# Sequencer2.net
KiCad netlist of a schematic drawn in EAGLE
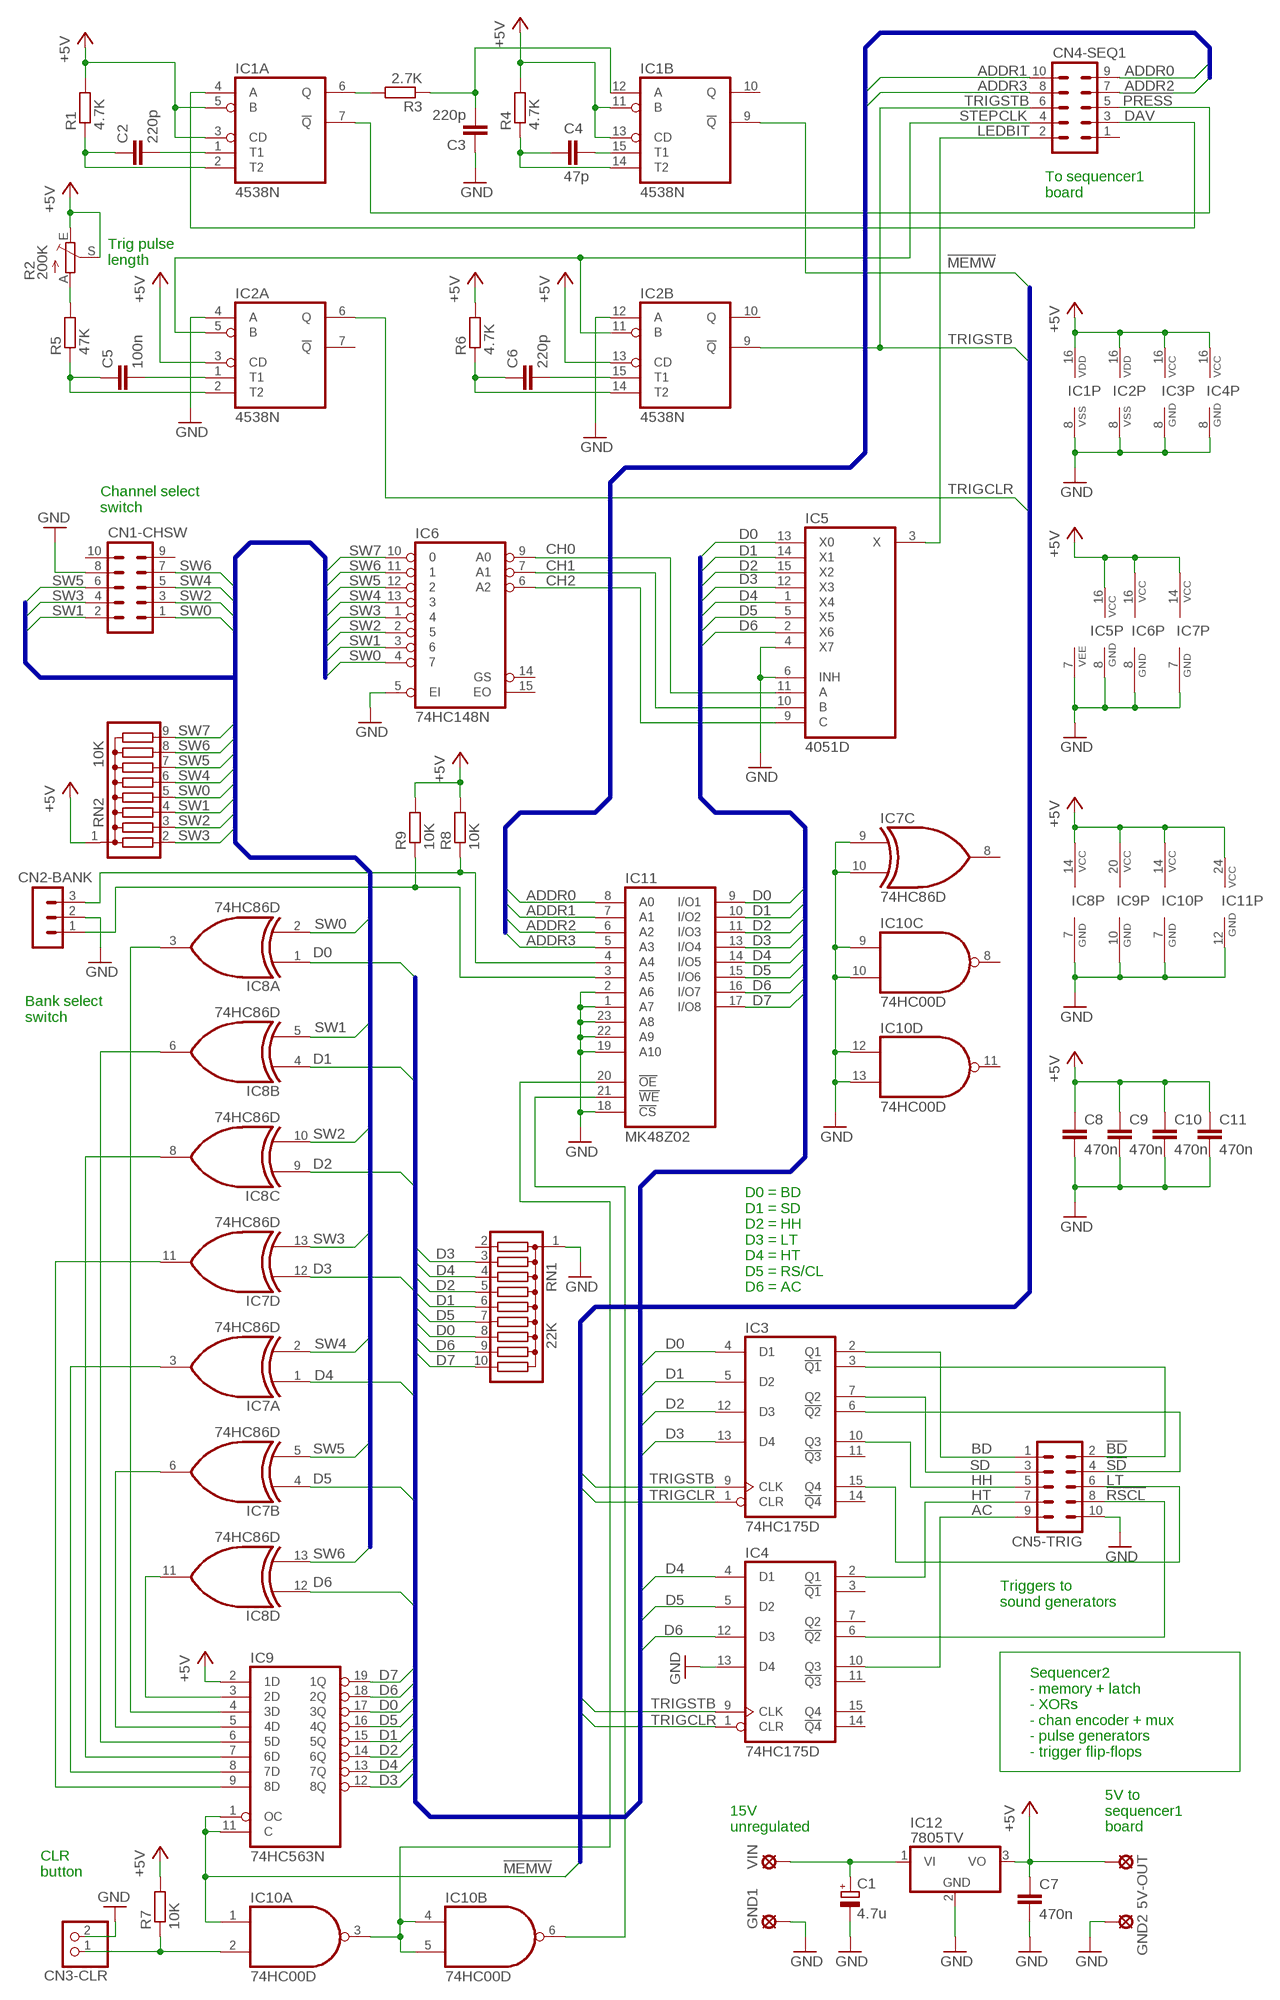
[diagram p0: schematic, sheet 1]

(export (version "E")
  (design (tool "Eeschema 10.0.6"))
  (components
    (comp (ref "5V-OUT")
      (value "LSP10")
      (footprint "eagle-import:LSP10")
      (libsource (lib "eagle-import") (part "LSP10"))
    )
    (comp (ref "C1")
      (value "4.7u")
      (footprint "eagle-import:SMC_A")
      (libsource (lib "eagle-import") (part "CPOL-EUSMCA"))
    )
    (comp (ref "C2")
      (value "220p")
      (footprint "eagle-import:C0805")
      (libsource (lib "eagle-import") (part "C-EUC0805"))
    )
    (comp (ref "C3")
      (value "220p")
      (footprint "eagle-import:C0805")
      (libsource (lib "eagle-import") (part "C-EUC0805"))
    )
    (comp (ref "C4")
      (value "47p")
      (footprint "eagle-import:C0805")
      (libsource (lib "eagle-import") (part "C-EUC0805"))
    )
    (comp (ref "C5")
      (value "100n")
      (footprint "eagle-import:C0805")
      (libsource (lib "eagle-import") (part "C-EUC0805"))
    )
    (comp (ref "C6")
      (value "220p")
      (footprint "eagle-import:C0805")
      (libsource (lib "eagle-import") (part "C-EUC0805"))
    )
    (comp (ref "C7")
      (value "470n")
      (footprint "eagle-import:C0603")
      (libsource (lib "eagle-import") (part "C-EUC0603"))
    )
    (comp (ref "C8")
      (value "470n")
      (footprint "eagle-import:C0603")
      (libsource (lib "eagle-import") (part "C-EUC0603"))
    )
    (comp (ref "C9")
      (value "470n")
      (footprint "eagle-import:C0603")
      (libsource (lib "eagle-import") (part "C-EUC0603"))
    )
    (comp (ref "C10")
      (value "470n")
      (footprint "eagle-import:C0603")
      (libsource (lib "eagle-import") (part "C-EUC0603"))
    )
    (comp (ref "C11")
      (value "470n")
      (footprint "eagle-import:C0603")
      (libsource (lib "eagle-import") (part "C-EUC0603"))
    )
    (comp (ref "CN1-CHSW")
      (value "MA05-2")
      (footprint "eagle-import:MA05-2")
      (libsource (lib "eagle-import") (part "MA05-2"))
    )
    (comp (ref "CN2-BANK")
      (value "MA03-1")
      (footprint "eagle-import:MA03-1")
      (libsource (lib "eagle-import") (part "MA03-1"))
    )
    (comp (ref "CN3-CLR")
      (value "PINHD-1X2")
      (footprint "eagle-import:1X02")
      (libsource (lib "eagle-import") (part "PINHD-1X2"))
    )
    (comp (ref "CN4-SEQ1")
      (value "MA05-2")
      (footprint "eagle-import:MA05-2")
      (libsource (lib "eagle-import") (part "MA05-2"))
    )
    (comp (ref "CN5-TRIG")
      (value "MA05-2")
      (footprint "eagle-import:MA05-2")
      (libsource (lib "eagle-import") (part "MA05-2"))
    )
    (comp (ref "GND1")
      (value "LSP10")
      (footprint "eagle-import:LSP10")
      (libsource (lib "eagle-import") (part "LSP10"))
    )
    (comp (ref "GND2")
      (value "LSP10")
      (footprint "eagle-import:LSP10")
      (libsource (lib "eagle-import") (part "LSP10"))
    )
    (comp (ref "IC1")
      (value "4538N")
      (footprint "eagle-import:DIL16")
      (libsource (lib "eagle-import") (part "4538N"))
    )
    (comp (ref "IC2")
      (value "4538N")
      (footprint "eagle-import:DIL16")
      (libsource (lib "eagle-import") (part "4538N"))
    )
    (comp (ref "IC3")
      (value "74HC175D")
      (footprint "eagle-import:SO16")
      (libsource (lib "eagle-import") (part "74175DHC"))
    )
    (comp (ref "IC4")
      (value "74HC175D")
      (footprint "eagle-import:SO16")
      (libsource (lib "eagle-import") (part "74175DHC"))
    )
    (comp (ref "IC5")
      (value "4051D")
      (footprint "eagle-import:SO16")
      (libsource (lib "eagle-import") (part "4051D"))
    )
    (comp (ref "IC6")
      (value "74HC148N")
      (footprint "eagle-import:DIL16")
      (libsource (lib "eagle-import") (part "74148NLS"))
    )
    (comp (ref "IC7")
      (value "74HC86D")
      (footprint "eagle-import:SO14")
      (libsource (lib "eagle-import") (part "7486DLS"))
    )
    (comp (ref "IC8")
      (value "74HC86D")
      (footprint "eagle-import:SO14")
      (libsource (lib "eagle-import") (part "7486DLS"))
    )
    (comp (ref "IC9")
      (value "74HC563N")
      (footprint "eagle-import:DIL20")
      (libsource (lib "eagle-import") (part "74563NHC"))
    )
    (comp (ref "IC10")
      (value "74HC00D")
      (footprint "eagle-import:SO14")
      (libsource (lib "eagle-import") (part "7400DALS"))
    )
    (comp (ref "IC11")
      (value "MK48Z02")
      (footprint "eagle-import:DIL24-6")
      (libsource (lib "eagle-import") (part "6116P"))
    )
    (comp (ref "IC12")
      (value "7805TV")
      (footprint "eagle-import:TO220V")
      (libsource (lib "eagle-import") (part "78TV05"))
    )
    (comp (ref "R1")
      (value "4.7K")
      (footprint "eagle-import:R0805")
      (libsource (lib "eagle-import") (part "R-EU_R0805"))
    )
    (comp (ref "R2")
      (value "200K")
      (footprint "eagle-import:S63X")
      (libsource (lib "eagle-import") (part "TRIM_EU-S63X"))
    )
    (comp (ref "R3")
      (value "2.7K")
      (footprint "eagle-import:R0805")
      (libsource (lib "eagle-import") (part "R-EU_R0805"))
    )
    (comp (ref "R4")
      (value "4.7K")
      (footprint "eagle-import:R0805")
      (libsource (lib "eagle-import") (part "R-EU_R0805"))
    )
    (comp (ref "R5")
      (value "47K")
      (footprint "eagle-import:R0805")
      (libsource (lib "eagle-import") (part "R-EU_R0805"))
    )
    (comp (ref "R6")
      (value "4.7K")
      (footprint "eagle-import:R0805")
      (libsource (lib "eagle-import") (part "R-EU_R0805"))
    )
    (comp (ref "R7")
      (value "10K")
      (footprint "eagle-import:R0805")
      (libsource (lib "eagle-import") (part "R-EU_R0805"))
    )
    (comp (ref "R8")
      (value "10K")
      (footprint "eagle-import:R0805")
      (libsource (lib "eagle-import") (part "R-EU_R0805"))
    )
    (comp (ref "R9")
      (value "10K")
      (footprint "eagle-import:R0805")
      (libsource (lib "eagle-import") (part "R-EU_R0805"))
    )
    (comp (ref "RN1")
      (value "22K")
      (footprint "eagle-import:SIL10")
      (libsource (lib "eagle-import") (part "G09R"))
    )
    (comp (ref "RN2")
      (value "10K")
      (footprint "eagle-import:SIL9")
      (libsource (lib "eagle-import") (part "G08R"))
    )
    (comp (ref "VIN")
      (value "LSP10")
      (footprint "eagle-import:LSP10")
      (libsource (lib "eagle-import") (part "LSP10"))
    )
  )
  (nets
    (net (code "1") (name "+5V") (class "Default")
      (node (ref "5V-OUT") (pin "MP") (pinfunction "MP_MP") (pintype "passive"))
      (node (ref "C10") (pin "1") (pinfunction "1_1") (pintype "passive"))
      (node (ref "C11") (pin "1") (pinfunction "1_1") (pintype "passive"))
      (node (ref "C7") (pin "1") (pinfunction "1_1") (pintype "passive"))
      (node (ref "C8") (pin "1") (pinfunction "1_1") (pintype "passive"))
      (node (ref "C9") (pin "1") (pinfunction "1_1") (pintype "passive"))
      (node (ref "IC1") (pin "11") (pinfunction "B_11") (pintype "input"))
      (node (ref "IC1") (pin "13") (pinfunction "CD_13") (pintype "input"))
      (node (ref "IC1") (pin "16") (pinfunction "VDD_16") (pintype "power_in"))
      (node (ref "IC1") (pin "3") (pinfunction "CD_3") (pintype "input"))
      (node (ref "IC1") (pin "5") (pinfunction "B_5") (pintype "input"))
      (node (ref "IC10") (pin "14") (pinfunction "VCC_14") (pintype "power_in"))
      (node (ref "IC11") (pin "24") (pinfunction "VCC_24") (pintype "power_in"))
      (node (ref "IC12") (pin "3") (pinfunction "VO_3") (pintype "passive"))
      (node (ref "IC2") (pin "13") (pinfunction "CD_13") (pintype "input"))
      (node (ref "IC2") (pin "16") (pinfunction "VDD_16") (pintype "power_in"))
      (node (ref "IC2") (pin "3") (pinfunction "CD_3") (pintype "input"))
      (node (ref "IC3") (pin "16") (pinfunction "VCC_16") (pintype "power_in"))
      (node (ref "IC4") (pin "16") (pinfunction "VCC_16") (pintype "power_in"))
      (node (ref "IC5") (pin "16") (pinfunction "VCC_16") (pintype "power_in"))
      (node (ref "IC6") (pin "16") (pinfunction "VCC_16") (pintype "power_in"))
      (node (ref "IC7") (pin "14") (pinfunction "VCC_14") (pintype "power_in"))
      (node (ref "IC8") (pin "14") (pinfunction "VCC_14") (pintype "power_in"))
      (node (ref "IC9") (pin "2") (pinfunction "1D_2") (pintype "input"))
      (node (ref "IC9") (pin "20") (pinfunction "VCC_20") (pintype "power_in"))
      (node (ref "R1") (pin "2") (pinfunction "2_2") (pintype "passive"))
      (node (ref "R2") (pin "E") (pinfunction "E_E") (pintype "passive"))
      (node (ref "R2") (pin "S") (pinfunction "S_S") (pintype "passive"))
      (node (ref "R4") (pin "2") (pinfunction "2_2") (pintype "passive"))
      (node (ref "R6") (pin "2") (pinfunction "2_2") (pintype "passive"))
      (node (ref "R7") (pin "2") (pinfunction "2_2") (pintype "passive"))
      (node (ref "R8") (pin "2") (pinfunction "2_2") (pintype "passive"))
      (node (ref "R9") (pin "2") (pinfunction "2_2") (pintype "passive"))
      (node (ref "RN2") (pin "1") (pinfunction "1_1") (pintype "passive"))
    )
    (net (code "2") (name "/AC") (class "Default")
      (node (ref "CN5-TRIG") (pin "9") (pinfunction "9_9") (pintype "passive"))
      (node (ref "IC4") (pin "10") (pinfunction "Q3_10") (pintype "output"))
    )
    (net (code "3") (name "/ADDR0") (class "Default")
      (node (ref "CN4-SEQ1") (pin "9") (pinfunction "9_9") (pintype "passive"))
      (node (ref "IC11") (pin "8") (pinfunction "A0_8") (pintype "input"))
    )
    (net (code "4") (name "/ADDR1") (class "Default")
      (node (ref "CN4-SEQ1") (pin "10") (pinfunction "10_10") (pintype "passive"))
      (node (ref "IC11") (pin "7") (pinfunction "A1_7") (pintype "input"))
    )
    (net (code "5") (name "/ADDR2") (class "Default")
      (node (ref "CN4-SEQ1") (pin "7") (pinfunction "7_7") (pintype "passive"))
      (node (ref "IC11") (pin "6") (pinfunction "A2_6") (pintype "input"))
    )
    (net (code "6") (name "/ADDR3") (class "Default")
      (node (ref "CN4-SEQ1") (pin "8") (pinfunction "8_8") (pintype "passive"))
      (node (ref "IC11") (pin "5") (pinfunction "A3_5") (pintype "input"))
    )
    (net (code "7") (name "/BD") (class "Default")
      (node (ref "CN5-TRIG") (pin "1") (pinfunction "1_1") (pintype "passive"))
      (node (ref "IC3") (pin "2") (pinfunction "Q1_2") (pintype "output"))
    )
    (net (code "8") (name "/CH0") (class "Default")
      (node (ref "IC5") (pin "11") (pinfunction "A_11") (pintype "input"))
      (node (ref "IC6") (pin "9") (pinfunction "A0_9") (pintype "output"))
    )
    (net (code "9") (name "/CH1") (class "Default")
      (node (ref "IC5") (pin "10") (pinfunction "B_10") (pintype "input"))
      (node (ref "IC6") (pin "7") (pinfunction "A1_7") (pintype "output"))
    )
    (net (code "10") (name "/CH2") (class "Default")
      (node (ref "IC5") (pin "9") (pinfunction "C_9") (pintype "input"))
      (node (ref "IC6") (pin "6") (pinfunction "A2_6") (pintype "output"))
    )
    (net (code "11") (name "/D0") (class "Default")
      (node (ref "IC11") (pin "9") (pinfunction "I/O1_9") (pintype "bidirectional"))
      (node (ref "IC3") (pin "4") (pinfunction "D1_4") (pintype "input"))
      (node (ref "IC5") (pin "13") (pinfunction "X0_13") (pintype "bidirectional"))
      (node (ref "IC8") (pin "1") (pinfunction "I0_1") (pintype "input"))
      (node (ref "IC9") (pin "17") (pinfunction "3Q_17") (pintype "tri_state"))
      (node (ref "RN1") (pin "8") (pinfunction "8_8") (pintype "passive"))
    )
    (net (code "12") (name "/D1") (class "Default")
      (node (ref "IC11") (pin "10") (pinfunction "I/O2_10") (pintype "bidirectional"))
      (node (ref "IC3") (pin "5") (pinfunction "D2_5") (pintype "input"))
      (node (ref "IC5") (pin "14") (pinfunction "X1_14") (pintype "bidirectional"))
      (node (ref "IC8") (pin "4") (pinfunction "I0_4") (pintype "input"))
      (node (ref "IC9") (pin "15") (pinfunction "5Q_15") (pintype "tri_state"))
      (node (ref "RN1") (pin "6") (pinfunction "6_6") (pintype "passive"))
    )
    (net (code "13") (name "/D2") (class "Default")
      (node (ref "IC11") (pin "11") (pinfunction "I/O3_11") (pintype "bidirectional"))
      (node (ref "IC3") (pin "12") (pinfunction "D3_12") (pintype "input"))
      (node (ref "IC5") (pin "15") (pinfunction "X2_15") (pintype "bidirectional"))
      (node (ref "IC8") (pin "9") (pinfunction "I0_9") (pintype "input"))
      (node (ref "IC9") (pin "14") (pinfunction "6Q_14") (pintype "tri_state"))
      (node (ref "RN1") (pin "5") (pinfunction "5_5") (pintype "passive"))
    )
    (net (code "14") (name "/D3") (class "Default")
      (node (ref "IC11") (pin "13") (pinfunction "I/O4_13") (pintype "bidirectional"))
      (node (ref "IC3") (pin "13") (pinfunction "D4_13") (pintype "input"))
      (node (ref "IC5") (pin "12") (pinfunction "X3_12") (pintype "bidirectional"))
      (node (ref "IC7") (pin "12") (pinfunction "I0_12") (pintype "input"))
      (node (ref "IC9") (pin "12") (pinfunction "8Q_12") (pintype "tri_state"))
      (node (ref "RN1") (pin "3") (pinfunction "3_3") (pintype "passive"))
    )
    (net (code "15") (name "/D4") (class "Default")
      (node (ref "IC11") (pin "14") (pinfunction "I/O5_14") (pintype "bidirectional"))
      (node (ref "IC4") (pin "4") (pinfunction "D1_4") (pintype "input"))
      (node (ref "IC5") (pin "1") (pinfunction "X4_1") (pintype "bidirectional"))
      (node (ref "IC7") (pin "1") (pinfunction "I0_1") (pintype "input"))
      (node (ref "IC9") (pin "13") (pinfunction "7Q_13") (pintype "tri_state"))
      (node (ref "RN1") (pin "4") (pinfunction "4_4") (pintype "passive"))
    )
    (net (code "16") (name "/D5") (class "Default")
      (node (ref "IC11") (pin "15") (pinfunction "I/O6_15") (pintype "bidirectional"))
      (node (ref "IC4") (pin "5") (pinfunction "D2_5") (pintype "input"))
      (node (ref "IC5") (pin "5") (pinfunction "X5_5") (pintype "bidirectional"))
      (node (ref "IC7") (pin "4") (pinfunction "I0_4") (pintype "input"))
      (node (ref "IC9") (pin "16") (pinfunction "4Q_16") (pintype "tri_state"))
      (node (ref "RN1") (pin "7") (pinfunction "7_7") (pintype "passive"))
    )
    (net (code "17") (name "/D6") (class "Default")
      (node (ref "IC11") (pin "16") (pinfunction "I/O7_16") (pintype "bidirectional"))
      (node (ref "IC4") (pin "12") (pinfunction "D3_12") (pintype "input"))
      (node (ref "IC5") (pin "2") (pinfunction "X6_2") (pintype "bidirectional"))
      (node (ref "IC8") (pin "12") (pinfunction "I0_12") (pintype "input"))
      (node (ref "IC9") (pin "18") (pinfunction "2Q_18") (pintype "tri_state"))
      (node (ref "RN1") (pin "9") (pinfunction "9_9") (pintype "passive"))
    )
    (net (code "18") (name "/D7") (class "Default")
      (node (ref "IC11") (pin "17") (pinfunction "I/O8_17") (pintype "bidirectional"))
      (node (ref "IC9") (pin "19") (pinfunction "1Q_19") (pintype "tri_state"))
      (node (ref "RN1") (pin "10") (pinfunction "10_10") (pintype "passive"))
    )
    (net (code "19") (name "/DAV") (class "Default")
      (node (ref "CN4-SEQ1") (pin "3") (pinfunction "3_3") (pintype "passive"))
      (node (ref "IC1") (pin "4") (pinfunction "A_4") (pintype "input"))
    )
    (net (code "20") (name "/HH") (class "Default")
      (node (ref "CN5-TRIG") (pin "5") (pinfunction "5_5") (pintype "passive"))
      (node (ref "IC3") (pin "10") (pinfunction "Q3_10") (pintype "output"))
    )
    (net (code "21") (name "/HT") (class "Default")
      (node (ref "CN5-TRIG") (pin "7") (pinfunction "7_7") (pintype "passive"))
      (node (ref "IC4") (pin "2") (pinfunction "Q1_2") (pintype "output"))
    )
    (net (code "22") (name "/LEDBIT") (class "Default")
      (node (ref "CN4-SEQ1") (pin "2") (pinfunction "2_2") (pintype "passive"))
      (node (ref "IC5") (pin "3") (pinfunction "X_3") (pintype "bidirectional"))
    )
    (net (code "23") (name "/LT") (class "Default")
      (node (ref "CN5-TRIG") (pin "6") (pinfunction "6_6") (pintype "passive"))
      (node (ref "IC3") (pin "15") (pinfunction "Q4_15") (pintype "output"))
    )
    (net (code "24") (name "/SD") (class "Default")
      (node (ref "CN5-TRIG") (pin "3") (pinfunction "3_3") (pintype "passive"))
      (node (ref "IC3") (pin "7") (pinfunction "Q2_7") (pintype "output"))
    )
    (net (code "25") (name "/STEPCLK") (class "Default")
      (node (ref "CN4-SEQ1") (pin "4") (pinfunction "4_4") (pintype "passive"))
      (node (ref "IC2") (pin "11") (pinfunction "B_11") (pintype "input"))
      (node (ref "IC2") (pin "5") (pinfunction "B_5") (pintype "input"))
    )
    (net (code "26") (name "/SW0") (class "Default")
      (node (ref "CN1-CHSW") (pin "1") (pinfunction "1_1") (pintype "passive"))
      (node (ref "IC6") (pin "4") (pinfunction "7_4") (pintype "input"))
      (node (ref "IC8") (pin "2") (pinfunction "I1_2") (pintype "input"))
      (node (ref "RN2") (pin "5") (pinfunction "5_5") (pintype "passive"))
    )
    (net (code "27") (name "/SW1") (class "Default")
      (node (ref "CN1-CHSW") (pin "2") (pinfunction "2_2") (pintype "passive"))
      (node (ref "IC6") (pin "3") (pinfunction "6_3") (pintype "input"))
      (node (ref "IC8") (pin "5") (pinfunction "I1_5") (pintype "input"))
      (node (ref "RN2") (pin "4") (pinfunction "4_4") (pintype "passive"))
    )
    (net (code "28") (name "/SW2") (class "Default")
      (node (ref "CN1-CHSW") (pin "3") (pinfunction "3_3") (pintype "passive"))
      (node (ref "IC6") (pin "2") (pinfunction "5_2") (pintype "input"))
      (node (ref "IC8") (pin "10") (pinfunction "I1_10") (pintype "input"))
      (node (ref "RN2") (pin "3") (pinfunction "3_3") (pintype "passive"))
    )
    (net (code "29") (name "/SW3") (class "Default")
      (node (ref "CN1-CHSW") (pin "4") (pinfunction "4_4") (pintype "passive"))
      (node (ref "IC6") (pin "1") (pinfunction "4_1") (pintype "input"))
      (node (ref "IC7") (pin "13") (pinfunction "I1_13") (pintype "input"))
      (node (ref "RN2") (pin "2") (pinfunction "2_2") (pintype "passive"))
    )
    (net (code "30") (name "/SW4") (class "Default")
      (node (ref "CN1-CHSW") (pin "5") (pinfunction "5_5") (pintype "passive"))
      (node (ref "IC6") (pin "13") (pinfunction "3_13") (pintype "input"))
      (node (ref "IC7") (pin "2") (pinfunction "I1_2") (pintype "input"))
      (node (ref "RN2") (pin "6") (pinfunction "6_6") (pintype "passive"))
    )
    (net (code "31") (name "/SW5") (class "Default")
      (node (ref "CN1-CHSW") (pin "6") (pinfunction "6_6") (pintype "passive"))
      (node (ref "IC6") (pin "12") (pinfunction "2_12") (pintype "input"))
      (node (ref "IC7") (pin "5") (pinfunction "I1_5") (pintype "input"))
      (node (ref "RN2") (pin "7") (pinfunction "7_7") (pintype "passive"))
    )
    (net (code "32") (name "/SW6") (class "Default")
      (node (ref "CN1-CHSW") (pin "7") (pinfunction "7_7") (pintype "passive"))
      (node (ref "IC6") (pin "11") (pinfunction "1_11") (pintype "input"))
      (node (ref "IC8") (pin "13") (pinfunction "I1_13") (pintype "input"))
      (node (ref "RN2") (pin "8") (pinfunction "8_8") (pintype "passive"))
    )
    (net (code "33") (name "/SW7") (class "Default")
      (node (ref "IC6") (pin "10") (pinfunction "0_10") (pintype "input"))
      (node (ref "RN2") (pin "9") (pinfunction "9_9") (pintype "passive"))
    )
    (net (code "34") (name "/TRIGCLR") (class "Default")
      (node (ref "IC2") (pin "6") (pinfunction "Q_6") (pintype "output"))
      (node (ref "IC3") (pin "1") (pinfunction "CLR_1") (pintype "input"))
      (node (ref "IC4") (pin "1") (pinfunction "CLR_1") (pintype "input"))
    )
    (net (code "35") (name "/TRIGSTB") (class "Default")
      (node (ref "CN4-SEQ1") (pin "6") (pinfunction "6_6") (pintype "passive"))
      (node (ref "IC2") (pin "9") (pinfunction "~{Q}_9") (pintype "output"))
      (node (ref "IC3") (pin "9") (pinfunction "CLK_9") (pintype "input"))
      (node (ref "IC4") (pin "9") (pinfunction "CLK_9") (pintype "input"))
    )
    (net (code "36") (name "/~{BD}") (class "Default")
      (node (ref "CN5-TRIG") (pin "2") (pinfunction "2_2") (pintype "passive"))
      (node (ref "IC3") (pin "3") (pinfunction "~{Q1}_3") (pintype "output"))
    )
    (net (code "37") (name "/~{MEMW}") (class "Default")
      (node (ref "IC1") (pin "9") (pinfunction "~{Q}_9") (pintype "output"))
      (node (ref "IC10") (pin "1") (pinfunction "I0_1") (pintype "input"))
      (node (ref "IC9") (pin "1") (pinfunction "OC_1") (pintype "input"))
      (node (ref "IC9") (pin "11") (pinfunction "C_11") (pintype "input"))
    )
    (net (code "38") (name "/~{PRESS}") (class "Default")
      (node (ref "CN4-SEQ1") (pin "5") (pinfunction "5_5") (pintype "passive"))
      (node (ref "IC1") (pin "7") (pinfunction "~{Q}_7") (pintype "output"))
    )
    (net (code "39") (name "/~{RSCL}") (class "Default")
      (node (ref "CN5-TRIG") (pin "8") (pinfunction "8_8") (pintype "passive"))
      (node (ref "IC4") (pin "6") (pinfunction "~{Q2}_6") (pintype "output"))
    )
    (net (code "40") (name "/~{SD}") (class "Default")
      (node (ref "CN5-TRIG") (pin "4") (pinfunction "4_4") (pintype "passive"))
      (node (ref "IC3") (pin "6") (pinfunction "~{Q2}_6") (pintype "output"))
    )
    (net (code "41") (name "GND") (class "Default")
      (node (ref "C1") (pin "-") (pinfunction "-_-") (pintype "passive"))
      (node (ref "C10") (pin "2") (pinfunction "2_2") (pintype "passive"))
      (node (ref "C11") (pin "2") (pinfunction "2_2") (pintype "passive"))
      (node (ref "C3") (pin "1") (pinfunction "1_1") (pintype "passive"))
      (node (ref "C7") (pin "2") (pinfunction "2_2") (pintype "passive"))
      (node (ref "C8") (pin "2") (pinfunction "2_2") (pintype "passive"))
      (node (ref "C9") (pin "2") (pinfunction "2_2") (pintype "passive"))
      (node (ref "CN1-CHSW") (pin "8") (pinfunction "8_8") (pintype "passive"))
      (node (ref "CN2-BANK") (pin "2") (pinfunction "2_2") (pintype "passive"))
      (node (ref "CN3-CLR") (pin "2") (pinfunction "2_2") (pintype "passive"))
      (node (ref "CN5-TRIG") (pin "10") (pinfunction "10_10") (pintype "passive"))
      (node (ref "GND1") (pin "MP") (pinfunction "MP_MP") (pintype "passive"))
      (node (ref "GND2") (pin "MP") (pinfunction "MP_MP") (pintype "passive"))
      (node (ref "IC1") (pin "8") (pinfunction "VSS_8") (pintype "power_in"))
      (node (ref "IC10") (pin "10") (pinfunction "I1_10") (pintype "input"))
      (node (ref "IC10") (pin "12") (pinfunction "I0_12") (pintype "input"))
      (node (ref "IC10") (pin "13") (pinfunction "I1_13") (pintype "input"))
      (node (ref "IC10") (pin "7") (pinfunction "GND_7") (pintype "power_in"))
      (node (ref "IC10") (pin "9") (pinfunction "I0_9") (pintype "input"))
      (node (ref "IC11") (pin "1") (pinfunction "A7_1") (pintype "input"))
      (node (ref "IC11") (pin "12") (pinfunction "GND_12") (pintype "power_in"))
      (node (ref "IC11") (pin "18") (pinfunction "~{CS}_18") (pintype "input"))
      (node (ref "IC11") (pin "19") (pinfunction "A10_19") (pintype "input"))
      (node (ref "IC11") (pin "2") (pinfunction "A6_2") (pintype "input"))
      (node (ref "IC11") (pin "22") (pinfunction "A9_22") (pintype "input"))
      (node (ref "IC11") (pin "23") (pinfunction "A8_23") (pintype "input"))
      (node (ref "IC12") (pin "2") (pinfunction "GND_2") (pintype "passive"))
      (node (ref "IC2") (pin "12") (pinfunction "A_12") (pintype "input"))
      (node (ref "IC2") (pin "4") (pinfunction "A_4") (pintype "input"))
      (node (ref "IC2") (pin "8") (pinfunction "VSS_8") (pintype "power_in"))
      (node (ref "IC3") (pin "8") (pinfunction "GND_8") (pintype "power_in"))
      (node (ref "IC4") (pin "13") (pinfunction "D4_13") (pintype "input"))
      (node (ref "IC4") (pin "8") (pinfunction "GND_8") (pintype "power_in"))
      (node (ref "IC5") (pin "4") (pinfunction "X7_4") (pintype "bidirectional"))
      (node (ref "IC5") (pin "6") (pinfunction "INH_6") (pintype "input"))
      (node (ref "IC5") (pin "7") (pinfunction "VEE_7") (pintype "power_in"))
      (node (ref "IC5") (pin "8") (pinfunction "GND_8") (pintype "power_in"))
      (node (ref "IC6") (pin "5") (pinfunction "EI_5") (pintype "input"))
      (node (ref "IC6") (pin "8") (pinfunction "GND_8") (pintype "power_in"))
      (node (ref "IC7") (pin "10") (pinfunction "I1_10") (pintype "input"))
      (node (ref "IC7") (pin "7") (pinfunction "GND_7") (pintype "power_in"))
      (node (ref "IC7") (pin "9") (pinfunction "I0_9") (pintype "input"))
      (node (ref "IC8") (pin "7") (pinfunction "GND_7") (pintype "power_in"))
      (node (ref "IC9") (pin "10") (pinfunction "GND_10") (pintype "power_in"))
      (node (ref "RN1") (pin "1") (pinfunction "1_1") (pintype "passive"))
    )
    (net (code "42") (name "Net-(IC1A-Q)") (class "Default")
      (node (ref "IC1") (pin "6") (pinfunction "Q_6") (pintype "output"))
      (node (ref "R3") (pin "2") (pinfunction "2_2") (pintype "passive"))
    )
    (net (code "43") (name "Net-(IC1A-T1)") (class "Default")
      (node (ref "C2") (pin "2") (pinfunction "2_2") (pintype "passive"))
      (node (ref "IC1") (pin "1") (pinfunction "T1_1") (pintype "input"))
    )
    (net (code "44") (name "Net-(IC1A-T2)") (class "Default")
      (node (ref "C2") (pin "1") (pinfunction "1_1") (pintype "passive"))
      (node (ref "IC1") (pin "2") (pinfunction "T2_2") (pintype "input"))
      (node (ref "R1") (pin "1") (pinfunction "1_1") (pintype "passive"))
    )
    (net (code "45") (name "Net-(IC1B-A)") (class "Default")
      (node (ref "C3") (pin "2") (pinfunction "2_2") (pintype "passive"))
      (node (ref "IC1") (pin "12") (pinfunction "A_12") (pintype "input"))
      (node (ref "R3") (pin "1") (pinfunction "1_1") (pintype "passive"))
    )
    (net (code "46") (name "Net-(IC1B-T1)") (class "Default")
      (node (ref "C4") (pin "1") (pinfunction "1_1") (pintype "passive"))
      (node (ref "IC1") (pin "15") (pinfunction "T1_15") (pintype "input"))
    )
    (net (code "47") (name "Net-(IC1B-T2)") (class "Default")
      (node (ref "C4") (pin "2") (pinfunction "2_2") (pintype "passive"))
      (node (ref "IC1") (pin "14") (pinfunction "T2_14") (pintype "input"))
      (node (ref "R4") (pin "1") (pinfunction "1_1") (pintype "passive"))
    )
    (net (code "48") (name "Net-(IC2A-T1)") (class "Default")
      (node (ref "C5") (pin "2") (pinfunction "2_2") (pintype "passive"))
      (node (ref "IC2") (pin "1") (pinfunction "T1_1") (pintype "input"))
    )
    (net (code "49") (name "Net-(IC2A-T2)") (class "Default")
      (node (ref "C5") (pin "1") (pinfunction "1_1") (pintype "passive"))
      (node (ref "IC2") (pin "2") (pinfunction "T2_2") (pintype "input"))
      (node (ref "R5") (pin "1") (pinfunction "1_1") (pintype "passive"))
    )
    (net (code "50") (name "Net-(IC2B-T1)") (class "Default")
      (node (ref "C6") (pin "2") (pinfunction "2_2") (pintype "passive"))
      (node (ref "IC2") (pin "15") (pinfunction "T1_15") (pintype "input"))
    )
    (net (code "51") (name "Net-(IC2B-T2)") (class "Default")
      (node (ref "C6") (pin "1") (pinfunction "1_1") (pintype "passive"))
      (node (ref "IC2") (pin "14") (pinfunction "T2_14") (pintype "input"))
      (node (ref "R6") (pin "1") (pinfunction "1_1") (pintype "passive"))
    )
    (net (code "52") (name "Net-(IC7A-O)") (class "Default")
      (node (ref "IC7") (pin "3") (pinfunction "O_3") (pintype "output"))
      (node (ref "IC9") (pin "8") (pinfunction "7D_8") (pintype "input"))
    )
    (net (code "53") (name "Net-(IC7B-O)") (class "Default")
      (node (ref "IC7") (pin "6") (pinfunction "O_6") (pintype "output"))
      (node (ref "IC9") (pin "5") (pinfunction "4D_5") (pintype "input"))
    )
    (net (code "54") (name "Net-(IC7D-O)") (class "Default")
      (node (ref "IC7") (pin "11") (pinfunction "O_11") (pintype "output"))
      (node (ref "IC9") (pin "9") (pinfunction "8D_9") (pintype "input"))
    )
    (net (code "55") (name "Net-(IC8A-O)") (class "Default")
      (node (ref "IC8") (pin "3") (pinfunction "O_3") (pintype "output"))
      (node (ref "IC9") (pin "4") (pinfunction "3D_4") (pintype "input"))
    )
    (net (code "56") (name "Net-(IC8B-O)") (class "Default")
      (node (ref "IC8") (pin "6") (pinfunction "O_6") (pintype "output"))
      (node (ref "IC9") (pin "6") (pinfunction "5D_6") (pintype "input"))
    )
    (net (code "57") (name "Net-(IC8C-O)") (class "Default")
      (node (ref "IC8") (pin "8") (pinfunction "O_8") (pintype "output"))
      (node (ref "IC9") (pin "7") (pinfunction "6D_7") (pintype "input"))
    )
    (net (code "58") (name "Net-(IC8D-O)") (class "Default")
      (node (ref "IC8") (pin "11") (pinfunction "O_11") (pintype "output"))
      (node (ref "IC9") (pin "3") (pinfunction "2D_3") (pintype "input"))
    )
    (net (code "59") (name "Net-(IC10A-I1)") (class "Default")
      (node (ref "CN3-CLR") (pin "1") (pinfunction "1_1") (pintype "passive"))
      (node (ref "IC10") (pin "2") (pinfunction "I1_2") (pintype "input"))
      (node (ref "R7") (pin "1") (pinfunction "1_1") (pintype "passive"))
    )
    (net (code "60") (name "Net-(IC10A-O)") (class "Default")
      (node (ref "IC10") (pin "3") (pinfunction "O_3") (pintype "output"))
      (node (ref "IC10") (pin "4") (pinfunction "I0_4") (pintype "input"))
      (node (ref "IC10") (pin "5") (pinfunction "I1_5") (pintype "input"))
      (node (ref "IC11") (pin "20") (pinfunction "~{OE}_20") (pintype "input"))
    )
    (net (code "61") (name "Net-(IC10B-O)") (class "Default")
      (node (ref "IC10") (pin "6") (pinfunction "O_6") (pintype "output"))
      (node (ref "IC11") (pin "21") (pinfunction "~{WE}_21") (pintype "input"))
    )
    (net (code "62") (name "Net-(IC11A-A4)") (class "Default")
      (node (ref "CN2-BANK") (pin "3") (pinfunction "3_3") (pintype "passive"))
      (node (ref "IC11") (pin "4") (pinfunction "A4_4") (pintype "input"))
      (node (ref "R8") (pin "1") (pinfunction "1_1") (pintype "passive"))
    )
    (net (code "63") (name "Net-(IC11A-A5)") (class "Default")
      (node (ref "CN2-BANK") (pin "1") (pinfunction "1_1") (pintype "passive"))
      (node (ref "IC11") (pin "3") (pinfunction "A5_3") (pintype "input"))
      (node (ref "R9") (pin "1") (pinfunction "1_1") (pintype "passive"))
    )
    (net (code "64") (name "Net-(IC12-VI)") (class "Default")
      (node (ref "C1") (pin "+") (pinfunction "+_+") (pintype "passive"))
      (node (ref "IC12") (pin "1") (pinfunction "VI_1") (pintype "input"))
      (node (ref "VIN") (pin "MP") (pinfunction "MP_MP") (pintype "passive"))
    )
    (net (code "65") (name "Net-(R2-PadA)") (class "Default")
      (node (ref "R2") (pin "A") (pinfunction "A_A") (pintype "passive"))
      (node (ref "R5") (pin "2") (pinfunction "2_2") (pintype "passive"))
    )
    (net (code "66") (name "unconnected-(CN1-CHSW-Pad9)") (class "Default")
      (node (ref "CN1-CHSW") (pin "9") (pinfunction "9_9") (pintype "passive"))
    )
    (net (code "67") (name "unconnected-(CN1-CHSW-Pad10)") (class "Default")
      (node (ref "CN1-CHSW") (pin "10") (pinfunction "10_10") (pintype "passive"))
    )
    (net (code "68") (name "unconnected-(CN4-SEQ1-Pad1)") (class "Default")
      (node (ref "CN4-SEQ1") (pin "1") (pinfunction "1_1") (pintype "passive"))
    )
    (net (code "69") (name "unconnected-(IC1B-Q-Pad10)") (class "Default")
      (node (ref "IC1") (pin "10") (pinfunction "Q_10") (pintype "output"))
    )
    (net (code "70") (name "unconnected-(IC2A-~{Q}-Pad7)") (class "Default")
      (node (ref "IC2") (pin "7") (pinfunction "~{Q}_7") (pintype "output"))
    )
    (net (code "71") (name "unconnected-(IC2B-Q-Pad10)") (class "Default")
      (node (ref "IC2") (pin "10") (pinfunction "Q_10") (pintype "output"))
    )
    (net (code "72") (name "unconnected-(IC3A-~{Q3}-Pad11)") (class "Default")
      (node (ref "IC3") (pin "11") (pinfunction "~{Q3}_11") (pintype "output"))
    )
    (net (code "73") (name "unconnected-(IC3A-~{Q4}-Pad14)") (class "Default")
      (node (ref "IC3") (pin "14") (pinfunction "~{Q4}_14") (pintype "output"))
    )
    (net (code "74") (name "unconnected-(IC4A-Q2-Pad7)") (class "Default")
      (node (ref "IC4") (pin "7") (pinfunction "Q2_7") (pintype "output"))
    )
    (net (code "75") (name "unconnected-(IC4A-Q4-Pad15)") (class "Default")
      (node (ref "IC4") (pin "15") (pinfunction "Q4_15") (pintype "output"))
    )
    (net (code "76") (name "unconnected-(IC4A-~{Q1}-Pad3)") (class "Default")
      (node (ref "IC4") (pin "3") (pinfunction "~{Q1}_3") (pintype "output"))
    )
    (net (code "77") (name "unconnected-(IC4A-~{Q3}-Pad11)") (class "Default")
      (node (ref "IC4") (pin "11") (pinfunction "~{Q3}_11") (pintype "output"))
    )
    (net (code "78") (name "unconnected-(IC4A-~{Q4}-Pad14)") (class "Default")
      (node (ref "IC4") (pin "14") (pinfunction "~{Q4}_14") (pintype "output"))
    )
    (net (code "79") (name "unconnected-(IC6A-EO-Pad15)") (class "Default")
      (node (ref "IC6") (pin "15") (pinfunction "EO_15") (pintype "output"))
    )
    (net (code "80") (name "unconnected-(IC6A-GS-Pad14)") (class "Default")
      (node (ref "IC6") (pin "14") (pinfunction "GS_14") (pintype "output"))
    )
    (net (code "81") (name "unconnected-(IC7C-O-Pad8)") (class "Default")
      (node (ref "IC7") (pin "8") (pinfunction "O_8") (pintype "output"))
    )
    (net (code "82") (name "unconnected-(IC10C-O-Pad8)") (class "Default")
      (node (ref "IC10") (pin "8") (pinfunction "O_8") (pintype "output"))
    )
    (net (code "83") (name "unconnected-(IC10D-O-Pad11)") (class "Default")
      (node (ref "IC10") (pin "11") (pinfunction "O_11") (pintype "output"))
    )
    (net (code "84") (name "unconnected-(RN1-Pad2)") (class "Default")
      (node (ref "RN1") (pin "2") (pinfunction "2_2") (pintype "passive"))
    )
  )
)
